# MCU_System.net
KiCad netlist of a schematic drawn in Altium Designer
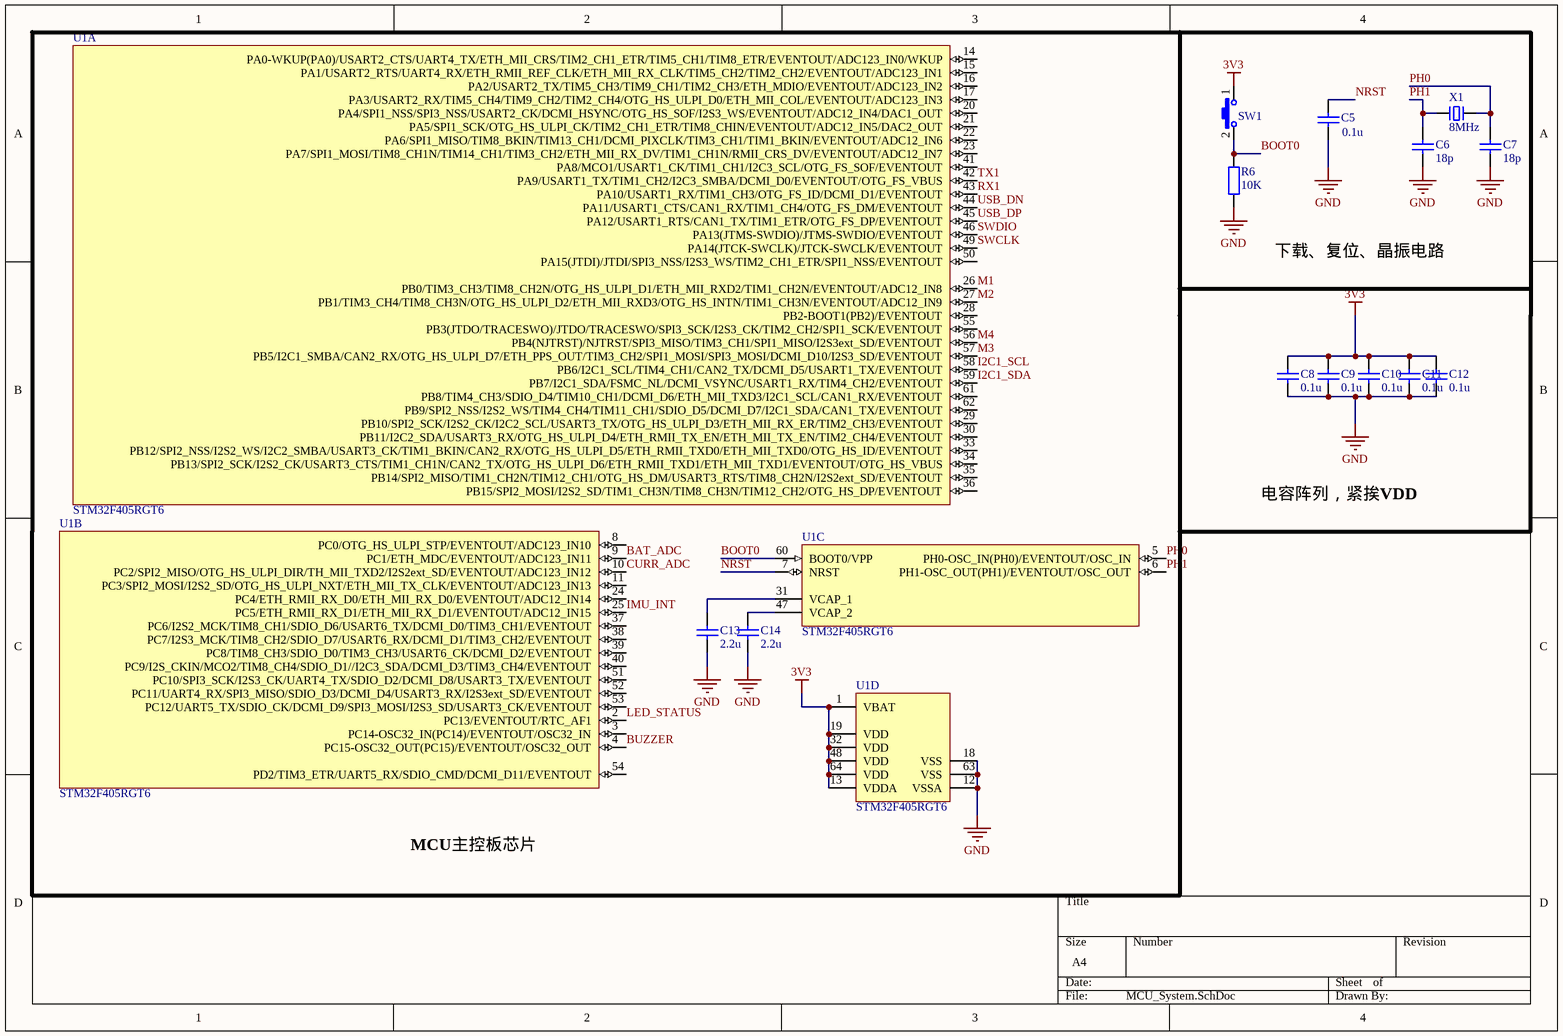
[diagram p0: MCU_System.SchDoc]

(export (version "E")
  (design (tool "Eeschema 10.0.6"))
  (components
    (comp (ref "C5")
      (value "0.1u")
      (footprint "C0402_M")
      (description "贴片电容/MLCC电容")
      (libsource (lib "0.1 - 电阻-电容-电感-保险丝-晶振-晶体-磁珠-电位器-法拉电容-馈通电容") (part "C"))
    )
    (comp (ref "C6")
      (value "18p")
      (footprint "C0402_M")
      (description "贴片电容/MLCC电容")
      (libsource (lib "0.1 - 电阻-电容-电感-保险丝-晶振-晶体-磁珠-电位器-法拉电容-馈通电容") (part "C"))
    )
    (comp (ref "C7")
      (value "18p")
      (footprint "C0402_M")
      (description "贴片电容/MLCC电容")
      (libsource (lib "0.1 - 电阻-电容-电感-保险丝-晶振-晶体-磁珠-电位器-法拉电容-馈通电容") (part "C"))
    )
    (comp (ref "C8")
      (value "0.1u")
      (footprint "C0402_M")
      (description "贴片电容/MLCC电容")
      (libsource (lib "0.1 - 电阻-电容-电感-保险丝-晶振-晶体-磁珠-电位器-法拉电容-馈通电容") (part "C"))
    )
    (comp (ref "C9")
      (value "0.1u")
      (footprint "C0402_M")
      (description "贴片电容/MLCC电容")
      (libsource (lib "0.1 - 电阻-电容-电感-保险丝-晶振-晶体-磁珠-电位器-法拉电容-馈通电容") (part "C"))
    )
    (comp (ref "C10")
      (value "0.1u")
      (footprint "C0402_M")
      (description "贴片电容/MLCC电容")
      (libsource (lib "0.1 - 电阻-电容-电感-保险丝-晶振-晶体-磁珠-电位器-法拉电容-馈通电容") (part "C"))
    )
    (comp (ref "C11")
      (value "0.1u")
      (footprint "C0402_M")
      (description "贴片电容/MLCC电容")
      (libsource (lib "0.1 - 电阻-电容-电感-保险丝-晶振-晶体-磁珠-电位器-法拉电容-馈通电容") (part "C"))
    )
    (comp (ref "C12")
      (value "0.1u")
      (footprint "C0402_M")
      (description "贴片电容/MLCC电容")
      (libsource (lib "0.1 - 电阻-电容-电感-保险丝-晶振-晶体-磁珠-电位器-法拉电容-馈通电容") (part "C"))
    )
    (comp (ref "C13")
      (value "2.2u")
      (footprint "C0402_M")
      (description "贴片电容/MLCC电容")
      (libsource (lib "0.1 - 电阻-电容-电感-保险丝-晶振-晶体-磁珠-电位器-法拉电容-馈通电容") (part "C"))
    )
    (comp (ref "C14")
      (value "2.2u")
      (footprint "C0402_M")
      (description "贴片电容/MLCC电容")
      (libsource (lib "0.1 - 电阻-电容-电感-保险丝-晶振-晶体-磁珠-电位器-法拉电容-馈通电容") (part "C"))
    )
    (comp (ref "R6")
      (value "10K")
      (footprint "R0402_M")
      (description "贴片电阻")
      (libsource (lib "0.1 - 电阻-电容-电感-保险丝-晶振-晶体-磁珠-电位器-法拉电容-馈通电容") (part "R"))
    )
    (comp (ref "SW1")
      (value "3x6x5")
      (footprint "SW-SMD-2.8*2.4_4P")
      (description "微动开关")
      (libsource (lib "0.5 - 按键_开关_蜂鸣器_电池_测试点_Mark点_铜柱") (part "SW-PB"))
    )
    (comp (ref "U1")
      (value "STM32F405RGT6")
      (footprint "TQFP64_M")
      (libsource (lib "2.7 - STM32 F4系列单片机") (part "STM32F405RGT6"))
    )
    (comp (ref "X1")
      (value "8MHz")
      (footprint "OSC-3225-4P")
      (description "2脚无源晶振(谐振器）")
      (libsource (lib "0.1 - 电阻-电容-电感-保险丝-晶振-晶体-磁珠-电位器-法拉电容-馈通电容") (part "XTAL-2P"))
    )
  )
  (nets
    (net (code "1") (name "/BAT_ADC") (class "Default")
      (node (ref "U1") (pin "9") (pinfunction "PC1/ETH_MDC/EVENTOUT/ADC123_IN11_9") (pintype "bidirectional"))
    )
    (net (code "2") (name "/BOOT0") (class "Default")
      (node (ref "R6") (pin "2") (pinfunction "2_2") (pintype "passive"))
      (node (ref "SW1") (pin "2") (pinfunction "2_2") (pintype "passive"))
      (node (ref "U1") (pin "60") (pinfunction "BOOT0/VPP_60") (pintype "input"))
    )
    (net (code "3") (name "/BUZZER") (class "Default")
      (node (ref "U1") (pin "4") (pinfunction "PC15-OSC32_OUT(PC15)/EVENTOUT/OSC32_OUT_4") (pintype "bidirectional"))
    )
    (net (code "4") (name "/CURR_ADC") (class "Default")
      (node (ref "U1") (pin "10") (pinfunction "PC2/SPI2_MISO/OTG_HS_ULPI_DIR/TH_MII_TXD2/I2S2ext_SD/EVENTOUT/ADC123_IN12_10") (pintype "bidirectional"))
    )
    (net (code "5") (name "/I2C1_SCL") (class "Default")
      (node (ref "U1") (pin "58") (pinfunction "PB6/I2C1_SCL/TIM4_CH1/CAN2_TX/DCMI_D5/USART1_TX/EVENTOUT_58") (pintype "bidirectional"))
    )
    (net (code "6") (name "/I2C1_SDA") (class "Default")
      (node (ref "U1") (pin "59") (pinfunction "PB7/I2C1_SDA/FSMC_NL/DCMI_VSYNC/USART1_RX/TIM4_CH2/EVENTOUT_59") (pintype "bidirectional"))
    )
    (net (code "7") (name "/IMU_INT") (class "Default")
      (node (ref "U1") (pin "25") (pinfunction "PC5/ETH_RMII_RX_D1/ETH_MII_RX_D1/EVENTOUT/ADC12_IN15_25") (pintype "bidirectional"))
    )
    (net (code "8") (name "/LED_STATUS") (class "Default")
      (node (ref "U1") (pin "2") (pinfunction "PC13/EVENTOUT/RTC_AF1_2") (pintype "bidirectional"))
    )
    (net (code "9") (name "/M1") (class "Default")
      (node (ref "U1") (pin "26") (pinfunction "PB0/TIM3_CH3/TIM8_CH2N/OTG_HS_ULPI_D1/ETH_MII_RXD2/TIM1_CH2N/EVENTOUT/ADC12_IN8_26") (pintype "bidirectional"))
    )
    (net (code "10") (name "/M2") (class "Default")
      (node (ref "U1") (pin "27") (pinfunction "PB1/TIM3_CH4/TIM8_CH3N/OTG_HS_ULPI_D2/ETH_MII_RXD3/OTG_HS_INTN/TIM1_CH3N/EVENTOUT/ADC12_IN9_27") (pintype "bidirectional"))
    )
    (net (code "11") (name "/M3") (class "Default")
      (node (ref "U1") (pin "57") (pinfunction "PB5/I2C1_SMBA/CAN2_RX/OTG_HS_ULPI_D7/ETH_PPS_OUT/TIM3_CH2/SPI1_MOSI/SPI3_MOSI/DCMI_D10/I2S3_SD/EVENTOUT_57") (pintype "bidirectional"))
    )
    (net (code "12") (name "/M4") (class "Default")
      (node (ref "U1") (pin "56") (pinfunction "PB4(NJTRST)/NJTRST/SPI3_MISO/TIM3_CH1/SPI1_MISO/I2S3ext_SD/EVENTOUT_56") (pintype "bidirectional"))
    )
    (net (code "13") (name "/NRST") (class "Default")
      (node (ref "C5") (pin "2") (pinfunction "2_2") (pintype "passive"))
      (node (ref "U1") (pin "7") (pinfunction "NRST_7") (pintype "bidirectional"))
    )
    (net (code "14") (name "/PH0") (class "Default")
      (node (ref "C7") (pin "2") (pinfunction "2_2") (pintype "passive"))
      (node (ref "U1") (pin "5") (pinfunction "PH0-OSC_IN(PH0)/EVENTOUT/OSC_IN_5") (pintype "bidirectional"))
      (node (ref "X1") (pin "3") (pinfunction "3_3") (pintype "passive"))
    )
    (net (code "15") (name "/PH1") (class "Default")
      (node (ref "C6") (pin "2") (pinfunction "2_2") (pintype "passive"))
      (node (ref "U1") (pin "6") (pinfunction "PH1-OSC_OUT(PH1)/EVENTOUT/OSC_OUT_6") (pintype "bidirectional"))
      (node (ref "X1") (pin "1") (pinfunction "1_1") (pintype "passive"))
    )
    (net (code "16") (name "/RX1") (class "Default")
      (node (ref "U1") (pin "43") (pinfunction "PA10/USART1_RX/TIM1_CH3/OTG_FS_ID/DCMI_D1/EVENTOUT_43") (pintype "bidirectional"))
    )
    (net (code "17") (name "/SWCLK") (class "Default")
      (node (ref "U1") (pin "49") (pinfunction "PA14(JTCK-SWCLK)/JTCK-SWCLK/EVENTOUT_49") (pintype "bidirectional"))
    )
    (net (code "18") (name "/SWDIO") (class "Default")
      (node (ref "U1") (pin "46") (pinfunction "PA13(JTMS-SWDIO)/JTMS-SWDIO/EVENTOUT_46") (pintype "bidirectional"))
    )
    (net (code "19") (name "/TX1") (class "Default")
      (node (ref "U1") (pin "42") (pinfunction "PA9/USART1_TX/TIM1_CH2/I2C3_SMBA/DCMI_D0/EVENTOUT/OTG_FS_VBUS_42") (pintype "bidirectional"))
    )
    (net (code "20") (name "/USB_DN") (class "Default")
      (node (ref "U1") (pin "44") (pinfunction "PA11/USART1_CTS/CAN1_RX/TIM1_CH4/OTG_FS_DM/EVENTOUT_44") (pintype "bidirectional"))
    )
    (net (code "21") (name "/USB_DP") (class "Default")
      (node (ref "U1") (pin "45") (pinfunction "PA12/USART1_RTS/CAN1_TX/TIM1_ETR/OTG_FS_DP/EVENTOUT_45") (pintype "bidirectional"))
    )
    (net (code "22") (name "3V3") (class "Default")
      (node (ref "C10") (pin "2") (pinfunction "2_2") (pintype "passive"))
      (node (ref "C11") (pin "2") (pinfunction "2_2") (pintype "passive"))
      (node (ref "C12") (pin "2") (pinfunction "2_2") (pintype "passive"))
      (node (ref "C8") (pin "2") (pinfunction "2_2") (pintype "passive"))
      (node (ref "C9") (pin "2") (pinfunction "2_2") (pintype "passive"))
      (node (ref "SW1") (pin "1") (pinfunction "1_1") (pintype "passive"))
      (node (ref "U1") (pin "1") (pinfunction "VBAT_1") (pintype "power_in"))
      (node (ref "U1") (pin "13") (pinfunction "VDDA_13") (pintype "power_in"))
      (node (ref "U1") (pin "19") (pinfunction "VDD_19") (pintype "power_in"))
      (node (ref "U1") (pin "32") (pinfunction "VDD_32") (pintype "power_in"))
      (node (ref "U1") (pin "48") (pinfunction "VDD_48") (pintype "power_in"))
      (node (ref "U1") (pin "64") (pinfunction "VDD_64") (pintype "power_in"))
    )
    (net (code "23") (name "GND") (class "Default")
      (node (ref "C10") (pin "1") (pinfunction "1_1") (pintype "passive"))
      (node (ref "C11") (pin "1") (pinfunction "1_1") (pintype "passive"))
      (node (ref "C12") (pin "1") (pinfunction "1_1") (pintype "passive"))
      (node (ref "C13") (pin "1") (pinfunction "1_1") (pintype "passive"))
      (node (ref "C14") (pin "1") (pinfunction "1_1") (pintype "passive"))
      (node (ref "C5") (pin "1") (pinfunction "1_1") (pintype "passive"))
      (node (ref "C6") (pin "1") (pinfunction "1_1") (pintype "passive"))
      (node (ref "C7") (pin "1") (pinfunction "1_1") (pintype "passive"))
      (node (ref "C8") (pin "1") (pinfunction "1_1") (pintype "passive"))
      (node (ref "C9") (pin "1") (pinfunction "1_1") (pintype "passive"))
      (node (ref "R6") (pin "1") (pinfunction "1_1") (pintype "passive"))
      (node (ref "U1") (pin "12") (pinfunction "VSSA_12") (pintype "power_in"))
      (node (ref "U1") (pin "18") (pinfunction "VSS_18") (pintype "power_in"))
      (node (ref "U1") (pin "63") (pinfunction "VSS_63") (pintype "power_in"))
    )
    (net (code "24") (name "Net-(U1C-VCAP_1)") (class "Default")
      (node (ref "C13") (pin "2") (pinfunction "2_2") (pintype "passive"))
      (node (ref "U1") (pin "31") (pinfunction "VCAP_1_31") (pintype "power_in"))
    )
    (net (code "25") (name "Net-(U1C-VCAP_2)") (class "Default")
      (node (ref "C14") (pin "2") (pinfunction "2_2") (pintype "passive"))
      (node (ref "U1") (pin "47") (pinfunction "VCAP_2_47") (pintype "power_in"))
    )
    (net (code "26") (name "unconnected-(U1A-PA0-WKUP(PA0){slash}USART2_CTS{slash}UART4_TX{slash}ETH_MII_CRS{slash}TIM2_CH1_ETR{slash}TIM5_CH1{slash}TIM8_ETR{slash}EVENTOUT{slash}ADC123_IN0{slash}WKUP-Pad14)") (class "Default")
      (node (ref "U1") (pin "14") (pinfunction "PA0-WKUP(PA0)/USART2_CTS/UART4_TX/ETH_MII_CRS/TIM2_CH1_ETR/TIM5_CH1/TIM8_ETR/EVENTOUT/ADC123_IN0/WKUP_14") (pintype "bidirectional"))
    )
    (net (code "27") (name "unconnected-(U1A-PA1{slash}USART2_RTS{slash}UART4_RX{slash}ETH_RMII_REF_CLK{slash}ETH_MII_RX_CLK{slash}TIM5_CH2{slash}TIM2_CH2{slash}EVENTOUT{slash}ADC123_IN1-Pad15)") (class "Default")
      (node (ref "U1") (pin "15") (pinfunction "PA1/USART2_RTS/UART4_RX/ETH_RMII_REF_CLK/ETH_MII_RX_CLK/TIM5_CH2/TIM2_CH2/EVENTOUT/ADC123_IN1_15") (pintype "bidirectional"))
    )
    (net (code "28") (name "unconnected-(U1A-PA2{slash}USART2_TX{slash}TIM5_CH3{slash}TIM9_CH1{slash}TIM2_CH3{slash}ETH_MDIO{slash}EVENTOUT{slash}ADC123_IN2-Pad16)") (class "Default")
      (node (ref "U1") (pin "16") (pinfunction "PA2/USART2_TX/TIM5_CH3/TIM9_CH1/TIM2_CH3/ETH_MDIO/EVENTOUT/ADC123_IN2_16") (pintype "bidirectional"))
    )
    (net (code "29") (name "unconnected-(U1A-PA3{slash}USART2_RX{slash}TIM5_CH4{slash}TIM9_CH2{slash}TIM2_CH4{slash}OTG_HS_ULPI_D0{slash}ETH_MII_COL{slash}EVENTOUT{slash}ADC123_IN3-Pad17)") (class "Default")
      (node (ref "U1") (pin "17") (pinfunction "PA3/USART2_RX/TIM5_CH4/TIM9_CH2/TIM2_CH4/OTG_HS_ULPI_D0/ETH_MII_COL/EVENTOUT/ADC123_IN3_17") (pintype "bidirectional"))
    )
    (net (code "30") (name "unconnected-(U1A-PA4{slash}SPI1_NSS{slash}SPI3_NSS{slash}USART2_CK{slash}DCMI_HSYNC{slash}OTG_HS_SOF{slash}I2S3_WS{slash}EVENTOUT{slash}ADC12_IN4{slash}DAC1_OUT-Pad20)") (class "Default")
      (node (ref "U1") (pin "20") (pinfunction "PA4/SPI1_NSS/SPI3_NSS/USART2_CK/DCMI_HSYNC/OTG_HS_SOF/I2S3_WS/EVENTOUT/ADC12_IN4/DAC1_OUT_20") (pintype "bidirectional"))
    )
    (net (code "31") (name "unconnected-(U1A-PA5{slash}SPI1_SCK{slash}OTG_HS_ULPI_CK{slash}TIM2_CH1_ETR{slash}TIM8_CHIN{slash}EVENTOUT{slash}ADC12_IN5{slash}DAC2_OUT-Pad21)") (class "Default")
      (node (ref "U1") (pin "21") (pinfunction "PA5/SPI1_SCK/OTG_HS_ULPI_CK/TIM2_CH1_ETR/TIM8_CHIN/EVENTOUT/ADC12_IN5/DAC2_OUT_21") (pintype "bidirectional"))
    )
    (net (code "32") (name "unconnected-(U1A-PA6{slash}SPI1_MISO{slash}TIM8_BKIN{slash}TIM13_CH1{slash}DCMI_PIXCLK{slash}TIM3_CH1{slash}TIM1_BKIN{slash}EVENTOUT{slash}ADC12_IN6-Pad22)") (class "Default")
      (node (ref "U1") (pin "22") (pinfunction "PA6/SPI1_MISO/TIM8_BKIN/TIM13_CH1/DCMI_PIXCLK/TIM3_CH1/TIM1_BKIN/EVENTOUT/ADC12_IN6_22") (pintype "bidirectional"))
    )
    (net (code "33") (name "unconnected-(U1A-PA7{slash}SPI1_MOSI{slash}TIM8_CH1N{slash}TIM14_CH1{slash}TIM3_CH2{slash}ETH_MII_RX_DV{slash}TIM1_CH1N{slash}RMII_CRS_DV{slash}EVENTOUT{slash}ADC12_IN7-Pad23)") (class "Default")
      (node (ref "U1") (pin "23") (pinfunction "PA7/SPI1_MOSI/TIM8_CH1N/TIM14_CH1/TIM3_CH2/ETH_MII_RX_DV/TIM1_CH1N/RMII_CRS_DV/EVENTOUT/ADC12_IN7_23") (pintype "bidirectional"))
    )
    (net (code "34") (name "unconnected-(U1A-PA8{slash}MCO1{slash}USART1_CK{slash}TIM1_CH1{slash}I2C3_SCL{slash}OTG_FS_SOF{slash}EVENTOUT-Pad41)") (class "Default")
      (node (ref "U1") (pin "41") (pinfunction "PA8/MCO1/USART1_CK/TIM1_CH1/I2C3_SCL/OTG_FS_SOF/EVENTOUT_41") (pintype "bidirectional"))
    )
    (net (code "35") (name "unconnected-(U1A-PA15(JTDI){slash}JTDI{slash}SPI3_NSS{slash}I2S3_WS{slash}TIM2_CH1_ETR{slash}SPI1_NSS{slash}EVENTOUT-Pad50)") (class "Default")
      (node (ref "U1") (pin "50") (pinfunction "PA15(JTDI)/JTDI/SPI3_NSS/I2S3_WS/TIM2_CH1_ETR/SPI1_NSS/EVENTOUT_50") (pintype "bidirectional"))
    )
    (net (code "36") (name "unconnected-(U1A-PB2-BOOT1(PB2){slash}EVENTOUT-Pad28)") (class "Default")
      (node (ref "U1") (pin "28") (pinfunction "PB2-BOOT1(PB2)/EVENTOUT_28") (pintype "bidirectional"))
    )
    (net (code "37") (name "unconnected-(U1A-PB3(JTDO{slash}TRACESWO){slash}JTDO{slash}TRACESWO{slash}SPI3_SCK{slash}I2S3_CK{slash}TIM2_CH2{slash}SPI1_SCK{slash}EVENTOUT-Pad55)") (class "Default")
      (node (ref "U1") (pin "55") (pinfunction "PB3(JTDO/TRACESWO)/JTDO/TRACESWO/SPI3_SCK/I2S3_CK/TIM2_CH2/SPI1_SCK/EVENTOUT_55") (pintype "bidirectional"))
    )
    (net (code "38") (name "unconnected-(U1A-PB8{slash}TIM4_CH3{slash}SDIO_D4{slash}TIM10_CH1{slash}DCMI_D6{slash}ETH_MII_TXD3{slash}I2C1_SCL{slash}CAN1_RX{slash}EVENTOUT-Pad61)") (class "Default")
      (node (ref "U1") (pin "61") (pinfunction "PB8/TIM4_CH3/SDIO_D4/TIM10_CH1/DCMI_D6/ETH_MII_TXD3/I2C1_SCL/CAN1_RX/EVENTOUT_61") (pintype "bidirectional"))
    )
    (net (code "39") (name "unconnected-(U1A-PB9{slash}SPI2_NSS{slash}I2S2_WS{slash}TIM4_CH4{slash}TIM11_CH1{slash}SDIO_D5{slash}DCMI_D7{slash}I2C1_SDA{slash}CAN1_TX{slash}EVENTOUT-Pad62)") (class "Default")
      (node (ref "U1") (pin "62") (pinfunction "PB9/SPI2_NSS/I2S2_WS/TIM4_CH4/TIM11_CH1/SDIO_D5/DCMI_D7/I2C1_SDA/CAN1_TX/EVENTOUT_62") (pintype "bidirectional"))
    )
    (net (code "40") (name "unconnected-(U1A-PB10{slash}SPI2_SCK{slash}I2S2_CK{slash}I2C2_SCL{slash}USART3_TX{slash}OTG_HS_ULPI_D3{slash}ETH_MII_RX_ER{slash}TIM2_CH3{slash}EVENTOUT-Pad29)") (class "Default")
      (node (ref "U1") (pin "29") (pinfunction "PB10/SPI2_SCK/I2S2_CK/I2C2_SCL/USART3_TX/OTG_HS_ULPI_D3/ETH_MII_RX_ER/TIM2_CH3/EVENTOUT_29") (pintype "bidirectional"))
    )
    (net (code "41") (name "unconnected-(U1A-PB11{slash}I2C2_SDA{slash}USART3_RX{slash}OTG_HS_ULPI_D4{slash}ETH_RMII_TX_EN{slash}ETH_MII_TX_EN{slash}TIM2_CH4{slash}EVENTOUT-Pad30)") (class "Default")
      (node (ref "U1") (pin "30") (pinfunction "PB11/I2C2_SDA/USART3_RX/OTG_HS_ULPI_D4/ETH_RMII_TX_EN/ETH_MII_TX_EN/TIM2_CH4/EVENTOUT_30") (pintype "bidirectional"))
    )
    (net (code "42") (name "unconnected-(U1A-PB12{slash}SPI2_NSS{slash}I2S2_WS{slash}I2C2_SMBA{slash}USART3_CK{slash}TIM1_BKIN{slash}CAN2_RX{slash}OTG_HS_ULPI_D5{slash}ETH_RMII_TXD0{slash}ETH_MII_TXD0{slash}OTG_HS_ID{slash}EVENTOUT-Pad33)") (class "Default")
      (node (ref "U1") (pin "33") (pinfunction "PB12/SPI2_NSS/I2S2_WS/I2C2_SMBA/USART3_CK/TIM1_BKIN/CAN2_RX/OTG_HS_ULPI_D5/ETH_RMII_TXD0/ETH_MII_TXD0/OTG_HS_ID/EVENTOUT_33") (pintype "bidirectional"))
    )
    (net (code "43") (name "unconnected-(U1A-PB13{slash}SPI2_SCK{slash}I2S2_CK{slash}USART3_CTS{slash}TIM1_CH1N{slash}CAN2_TX{slash}OTG_HS_ULPI_D6{slash}ETH_RMII_TXD1{slash}ETH_MII_TXD1{slash}EVENTOUT{slash}OTG_HS_VBUS-Pad34)") (class "Default")
      (node (ref "U1") (pin "34") (pinfunction "PB13/SPI2_SCK/I2S2_CK/USART3_CTS/TIM1_CH1N/CAN2_TX/OTG_HS_ULPI_D6/ETH_RMII_TXD1/ETH_MII_TXD1/EVENTOUT/OTG_HS_VBUS_34") (pintype "bidirectional"))
    )
    (net (code "44") (name "unconnected-(U1A-PB14{slash}SPI2_MISO{slash}TIM1_CH2N{slash}TIM12_CH1{slash}OTG_HS_DM{slash}USART3_RTS{slash}TIM8_CH2N{slash}I2S2ext_SD{slash}EVENTOUT-Pad35)") (class "Default")
      (node (ref "U1") (pin "35") (pinfunction "PB14/SPI2_MISO/TIM1_CH2N/TIM12_CH1/OTG_HS_DM/USART3_RTS/TIM8_CH2N/I2S2ext_SD/EVENTOUT_35") (pintype "bidirectional"))
    )
    (net (code "45") (name "unconnected-(U1A-PB15{slash}SPI2_MOSI{slash}I2S2_SD{slash}TIM1_CH3N{slash}TIM8_CH3N{slash}TIM12_CH2{slash}OTG_HS_DP{slash}EVENTOUT-Pad36)") (class "Default")
      (node (ref "U1") (pin "36") (pinfunction "PB15/SPI2_MOSI/I2S2_SD/TIM1_CH3N/TIM8_CH3N/TIM12_CH2/OTG_HS_DP/EVENTOUT_36") (pintype "bidirectional"))
    )
    (net (code "46") (name "unconnected-(U1B-PC0{slash}OTG_HS_ULPI_STP{slash}EVENTOUT{slash}ADC123_IN10-Pad8)") (class "Default")
      (node (ref "U1") (pin "8") (pinfunction "PC0/OTG_HS_ULPI_STP/EVENTOUT/ADC123_IN10_8") (pintype "bidirectional"))
    )
    (net (code "47") (name "unconnected-(U1B-PC3{slash}SPI2_MOSI{slash}I2S2_SD{slash}OTG_HS_ULPI_NXT{slash}ETH_MII_TX_CLK{slash}EVENTOUT{slash}ADC123_IN13-Pad11)") (class "Default")
      (node (ref "U1") (pin "11") (pinfunction "PC3/SPI2_MOSI/I2S2_SD/OTG_HS_ULPI_NXT/ETH_MII_TX_CLK/EVENTOUT/ADC123_IN13_11") (pintype "bidirectional"))
    )
    (net (code "48") (name "unconnected-(U1B-PC4{slash}ETH_RMII_RX_D0{slash}ETH_MII_RX_D0{slash}EVENTOUT{slash}ADC12_IN14-Pad24)") (class "Default")
      (node (ref "U1") (pin "24") (pinfunction "PC4/ETH_RMII_RX_D0/ETH_MII_RX_D0/EVENTOUT/ADC12_IN14_24") (pintype "bidirectional"))
    )
    (net (code "49") (name "unconnected-(U1B-PC6{slash}I2S2_MCK{slash}TIM8_CH1{slash}SDIO_D6{slash}USART6_TX{slash}DCMI_D0{slash}TIM3_CH1{slash}EVENTOUT-Pad37)") (class "Default")
      (node (ref "U1") (pin "37") (pinfunction "PC6/I2S2_MCK/TIM8_CH1/SDIO_D6/USART6_TX/DCMI_D0/TIM3_CH1/EVENTOUT_37") (pintype "bidirectional"))
    )
    (net (code "50") (name "unconnected-(U1B-PC7{slash}I2S3_MCK{slash}TIM8_CH2{slash}SDIO_D7{slash}USART6_RX{slash}DCMI_D1{slash}TIM3_CH2{slash}EVENTOUT-Pad38)") (class "Default")
      (node (ref "U1") (pin "38") (pinfunction "PC7/I2S3_MCK/TIM8_CH2/SDIO_D7/USART6_RX/DCMI_D1/TIM3_CH2/EVENTOUT_38") (pintype "bidirectional"))
    )
    (net (code "51") (name "unconnected-(U1B-PC8{slash}TIM8_CH3{slash}SDIO_D0{slash}TIM3_CH3{slash}USART6_CK{slash}DCMI_D2{slash}EVENTOUT-Pad39)") (class "Default")
      (node (ref "U1") (pin "39") (pinfunction "PC8/TIM8_CH3/SDIO_D0/TIM3_CH3/USART6_CK/DCMI_D2/EVENTOUT_39") (pintype "bidirectional"))
    )
    (net (code "52") (name "unconnected-(U1B-PC9{slash}I2S_CKIN{slash}MCO2{slash}TIM8_CH4{slash}SDIO_D1{slash}{slash}I2C3_SDA{slash}DCMI_D3{slash}TIM3_CH4{slash}EVENTOUT-Pad40)") (class "Default")
      (node (ref "U1") (pin "40") (pinfunction "PC9/I2S_CKIN/MCO2/TIM8_CH4/SDIO_D1//I2C3_SDA/DCMI_D3/TIM3_CH4/EVENTOUT_40") (pintype "bidirectional"))
    )
    (net (code "53") (name "unconnected-(U1B-PC10{slash}SPI3_SCK{slash}I2S3_CK{slash}UART4_TX{slash}SDIO_D2{slash}DCMI_D8{slash}USART3_TX{slash}EVENTOUT-Pad51)") (class "Default")
      (node (ref "U1") (pin "51") (pinfunction "PC10/SPI3_SCK/I2S3_CK/UART4_TX/SDIO_D2/DCMI_D8/USART3_TX/EVENTOUT_51") (pintype "bidirectional"))
    )
    (net (code "54") (name "unconnected-(U1B-PC11{slash}UART4_RX{slash}SPI3_MISO{slash}SDIO_D3{slash}DCMI_D4{slash}USART3_RX{slash}I2S3ext_SD{slash}EVENTOUT-Pad52)") (class "Default")
      (node (ref "U1") (pin "52") (pinfunction "PC11/UART4_RX/SPI3_MISO/SDIO_D3/DCMI_D4/USART3_RX/I2S3ext_SD/EVENTOUT_52") (pintype "bidirectional"))
    )
    (net (code "55") (name "unconnected-(U1B-PC12{slash}UART5_TX{slash}SDIO_CK{slash}DCMI_D9{slash}SPI3_MOSI{slash}I2S3_SD{slash}USART3_CK{slash}EVENTOUT-Pad53)") (class "Default")
      (node (ref "U1") (pin "53") (pinfunction "PC12/UART5_TX/SDIO_CK/DCMI_D9/SPI3_MOSI/I2S3_SD/USART3_CK/EVENTOUT_53") (pintype "bidirectional"))
    )
    (net (code "56") (name "unconnected-(U1B-PC14-OSC32_IN(PC14){slash}EVENTOUT{slash}OSC32_IN-Pad3)") (class "Default")
      (node (ref "U1") (pin "3") (pinfunction "PC14-OSC32_IN(PC14)/EVENTOUT/OSC32_IN_3") (pintype "bidirectional"))
    )
    (net (code "57") (name "unconnected-(U1B-PD2{slash}TIM3_ETR{slash}UART5_RX{slash}SDIO_CMD{slash}DCMI_D11{slash}EVENTOUT-Pad54)") (class "Default")
      (node (ref "U1") (pin "54") (pinfunction "PD2/TIM3_ETR/UART5_RX/SDIO_CMD/DCMI_D11/EVENTOUT_54") (pintype "bidirectional"))
    )
  )
)
